# RF.net
KiCad netlist of a schematic drawn in Altium Designer
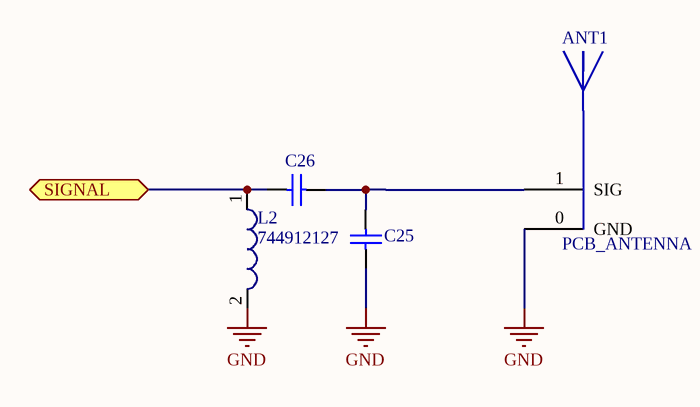
[diagram p0: RF.SchDoc]

(export (version "E")
  (design (tool "Eeschema 10.0.6"))
  (components
    (comp (ref "ANT1")
      (value "PCB_ANTENNA")
      (footprint "2.4GHZ_ANTENNA")
      (libsource (lib "Water Heater Components") (part "PCB_ANTENNA"))
    )
    (comp (ref "C25")
      (value "CAP 2.4pF 100V 0603(1608)")
      (footprint "CAPC0603(1608)100_L")
      (description "CAP 2.4pF 100V ±0.25pF 0603 (1608 Metric) Thickness 1mm SMD")
      (fields (field (name "TOLERANCE") "Â±0.25pF"))
      (libsource (lib "Altium Content Vault") (part "CMP-1035-00176-1"))
    )
    (comp (ref "C26")
      (value "CAP 3.9pF 100V 0603(1608)")
      (footprint "CAPC0603(1608)100_N")
      (description "CAP 3.9pF 100V ±0.1pF 0603 (1608 Metric) Thickness 1mm SMD")
      (fields (field (name "TOLERANCE") "Â±0.1pF"))
      (libsource (lib "Altium Content Vault") (part "CMP-1035-00286-1"))
    )
    (comp (ref "L2")
      (value "744912127")
      (footprint "WE-CAIR_4248")
      (description "WE-CAIR Air Coil, L=27 nH")
      (fields (field (name "MANUFACTURER") "Wuerth Elektronik"))
      (libsource (lib "Altium Content Vault") (part "CMP-1497-00015-1"))
    )
  )
  (nets
    (net (code "1") (name "/SIGNAL") (class "Default")
      (node (ref "C26") (pin "1") (pinfunction "1_1") (pintype "passive"))
      (node (ref "L2") (pin "1") (pinfunction "1_1") (pintype "passive"))
    )
    (net (code "2") (name "GND") (class "Default")
      (node (ref "ANT1") (pin "0") (pinfunction "GND_0") (pintype "passive"))
      (node (ref "C25") (pin "1") (pinfunction "1_1") (pintype "passive"))
      (node (ref "L2") (pin "2") (pinfunction "2_2") (pintype "passive"))
    )
    (net (code "3") (name "Net-(ANT1-SIG)") (class "Default")
      (node (ref "ANT1") (pin "1") (pinfunction "SIG_1") (pintype "passive"))
      (node (ref "C25") (pin "2") (pinfunction "2_2") (pintype "passive"))
      (node (ref "C26") (pin "2") (pinfunction "2_2") (pintype "passive"))
    )
  )
)
